# IOTBee-Carrier_v0_1.net
KiCad netlist of a schematic drawn in EAGLE
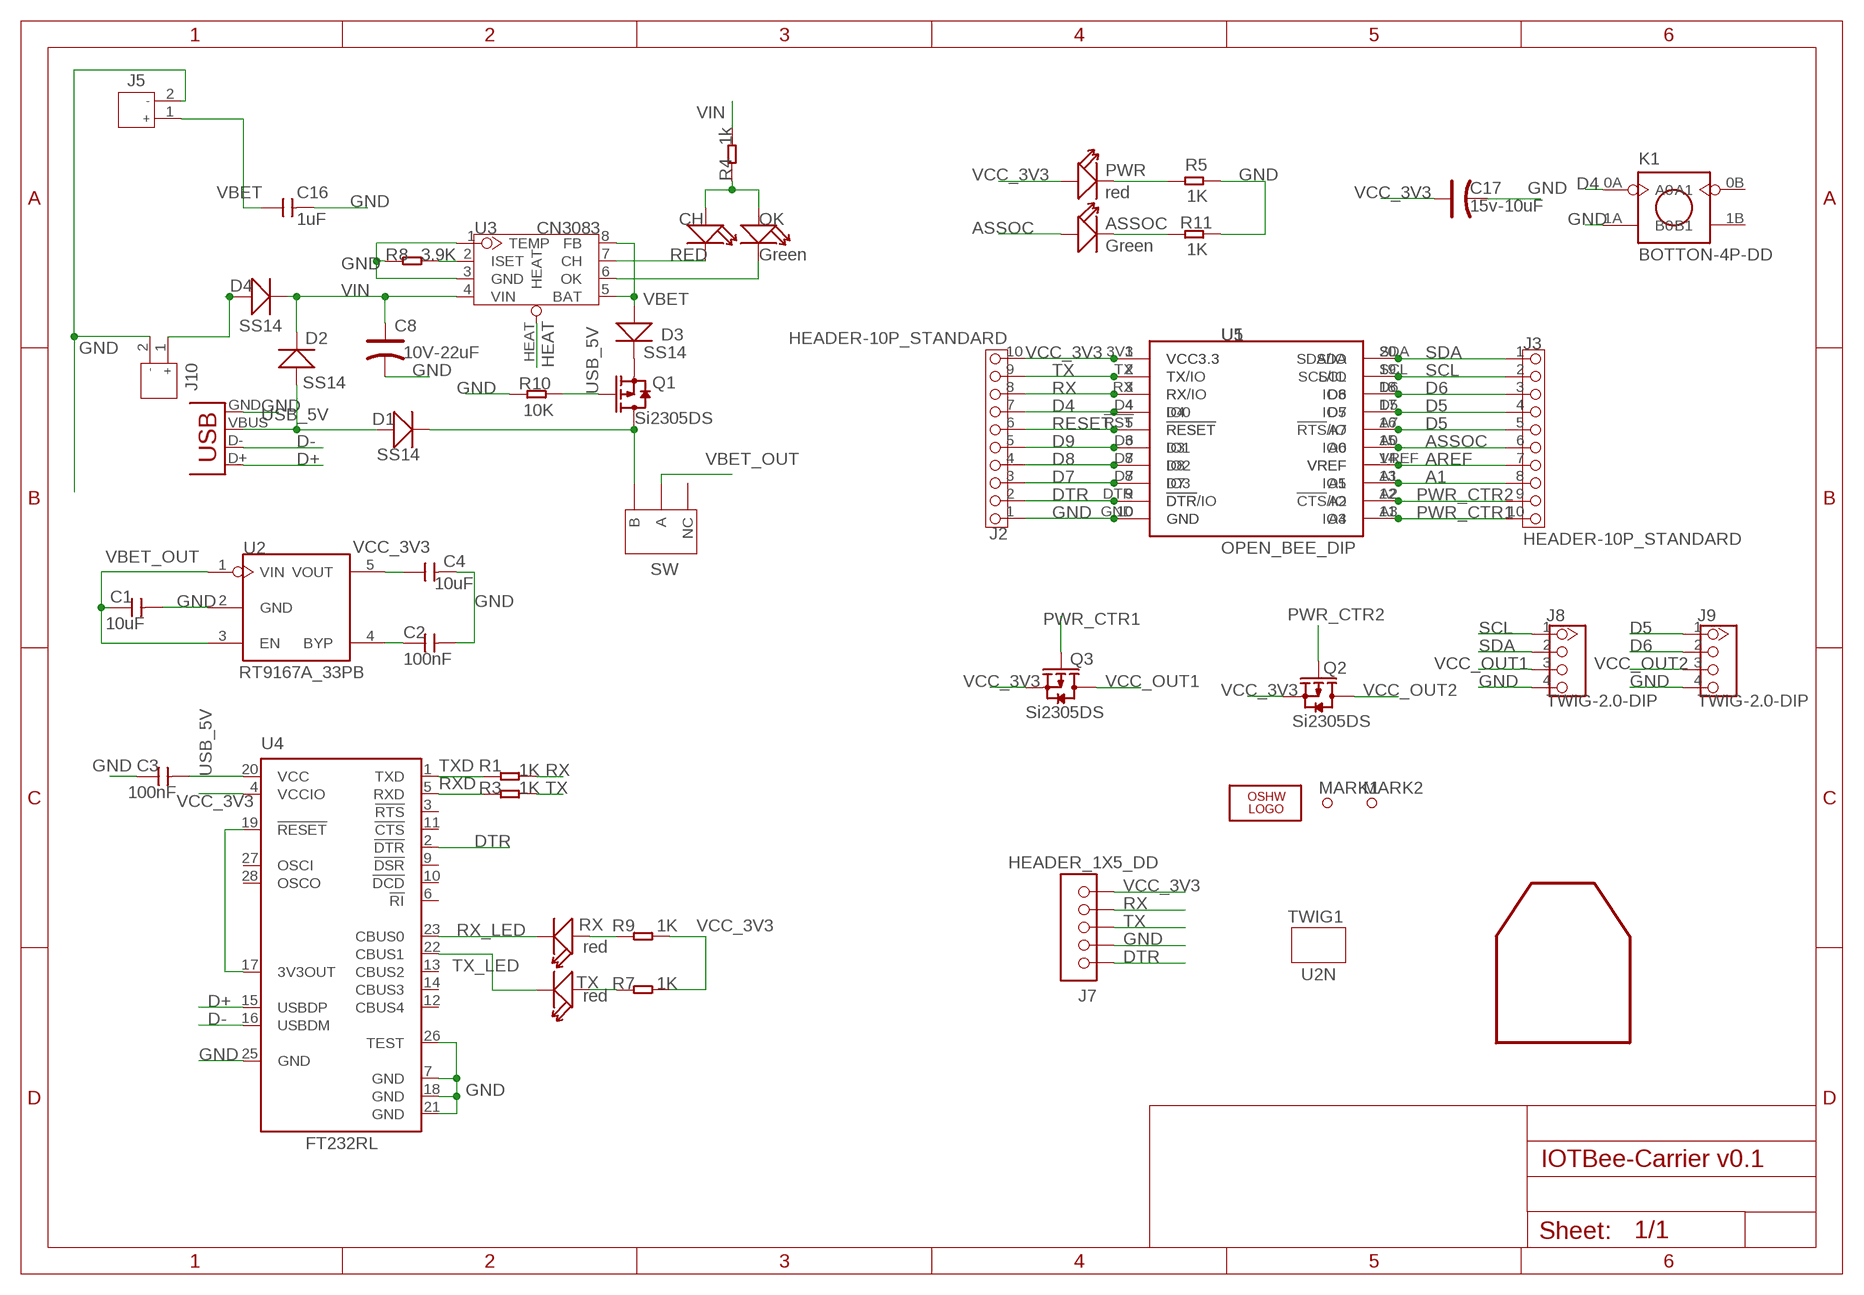
[diagram p0: schematic, sheet 1]

(export (version "E")
  (design (tool "Eeschema 10.0.6"))
  (components
    (comp (ref "ASSOC")
      (value "Green")
      (footprint "eagle-import:D0603")
      (libsource (lib "eagle-import") (part "LED-0603"))
    )
    (comp (ref "C1")
      (value "10uF")
      (footprint "eagle-import:0805")
      (libsource (lib "eagle-import") (part "C-0805"))
    )
    (comp (ref "C2")
      (value "100nF")
      (footprint "eagle-import:0603")
      (libsource (lib "eagle-import") (part "C-0603"))
    )
    (comp (ref "C3")
      (value "100nF")
      (footprint "eagle-import:0603")
      (libsource (lib "eagle-import") (part "C-0603"))
    )
    (comp (ref "C4")
      (value "10uF")
      (footprint "eagle-import:0805")
      (libsource (lib "eagle-import") (part "C-0805"))
    )
    (comp (ref "C8")
      (value "10V-22uF")
      (footprint "eagle-import:AVX-B")
      (libsource (lib "eagle-import") (part "CAP_AVX_B"))
    )
    (comp (ref "C16")
      (value "1uF")
      (footprint "eagle-import:0805")
      (libsource (lib "eagle-import") (part "C-0805"))
    )
    (comp (ref "C17")
      (value "15v-10uF")
      (footprint "eagle-import:AVX-A")
      (libsource (lib "eagle-import") (part "CAP_AVX_A"))
    )
    (comp (ref "CH")
      (value "RED")
      (footprint "eagle-import:D0603")
      (libsource (lib "eagle-import") (part "LED-0603"))
    )
    (comp (ref "D1")
      (value "SS14")
      (footprint "eagle-import:D2010")
      (libsource (lib "eagle-import") (part "D-2010"))
    )
    (comp (ref "D2")
      (value "SS14")
      (footprint "eagle-import:D2010")
      (libsource (lib "eagle-import") (part "D-2010"))
    )
    (comp (ref "D3")
      (value "SS14")
      (footprint "eagle-import:D2010")
      (libsource (lib "eagle-import") (part "D-2010"))
    )
    (comp (ref "D4")
      (value "SS14")
      (footprint "eagle-import:D2010")
      (libsource (lib "eagle-import") (part "D-2010"))
    )
    (comp (ref "J2")
      (value "HEADER-10P_STANDARD")
      (footprint "eagle-import:2.54_10P")
      (libsource (lib "eagle-import") (part "HEADER-10P_STANDARD"))
    )
    (comp (ref "J3")
      (value "HEADER-10P_STANDARD")
      (footprint "eagle-import:2.54_10P")
      (libsource (lib "eagle-import") (part "HEADER-10P_STANDARD"))
    )
    (comp (ref "J5")
      (value "JST-2P-POWER-LEADED")
      (footprint "eagle-import:2P-2.0-LEADED-4.7X6.0")
      (libsource (lib "eagle-import") (part "JST-2P-POWER-LEADED"))
    )
    (comp (ref "J7")
      (value "HEADER_1X5_DD")
      (footprint "eagle-import:CK_1X5")
      (libsource (lib "eagle-import") (part "HEADER_1X5_DD"))
    )
    (comp (ref "J8")
      (value "TWIG-2.0-DIP")
      (footprint "eagle-import:2.0_1X4")
      (libsource (lib "eagle-import") (part "TWIG-2.0-DIP"))
    )
    (comp (ref "J9")
      (value "TWIG-2.0-DIP")
      (footprint "eagle-import:2.0_1X4")
      (libsource (lib "eagle-import") (part "TWIG-2.0-DIP"))
    )
    (comp (ref "J10")
      (value "JST-2P-POWER-LEADED")
      (footprint "eagle-import:2P-2.0-LEADED-4.7X6.0")
      (libsource (lib "eagle-import") (part "JST-2P-POWER-LEADED"))
    )
    (comp (ref "K1")
      (value "BOTTON-4P-DD")
      (footprint "eagle-import:BTN-S")
      (libsource (lib "eagle-import") (part "BOTTON-4P-DD"))
    )
    (comp (ref "LOGO2")
      (value "OSHW_LOGO_FILLX0200-NT")
      (footprint "eagle-import:OSHW_FILLX200_NOTEXT")
      (libsource (lib "eagle-import") (part "OSHW_LOGO_FILLX0200-NT"))
    )
    (comp (ref "MARK1")
      (value "PAD-MARK")
      (footprint "eagle-import:MARK")
      (libsource (lib "eagle-import") (part "PAD-MARK"))
    )
    (comp (ref "MARK2")
      (value "PAD-MARK")
      (footprint "eagle-import:MARK")
      (libsource (lib "eagle-import") (part "PAD-MARK"))
    )
    (comp (ref "OK")
      (value "Green")
      (footprint "eagle-import:D0603")
      (libsource (lib "eagle-import") (part "LED-0603"))
    )
    (comp (ref "PWR")
      (value "red")
      (footprint "eagle-import:D0805")
      (libsource (lib "eagle-import") (part "LED-0805"))
    )
    (comp (ref "Q1")
      (value "Si2305DS")
      (footprint "eagle-import:SOT23")
      (libsource (lib "eagle-import") (part "010-P-MOSFETSOT23"))
    )
    (comp (ref "Q2")
      (value "Si2305DS")
      (footprint "eagle-import:SOT23")
      (libsource (lib "eagle-import") (part "010-P-MOSFETSOT23"))
    )
    (comp (ref "Q3")
      (value "Si2305DS")
      (footprint "eagle-import:SOT23")
      (libsource (lib "eagle-import") (part "010-P-MOSFETSOT23"))
    )
    (comp (ref "R1")
      (value "1K")
      (footprint "eagle-import:0603")
      (libsource (lib "eagle-import") (part "R-0603"))
    )
    (comp (ref "R3")
      (value "1K")
      (footprint "eagle-import:0603")
      (libsource (lib "eagle-import") (part "R-0603"))
    )
    (comp (ref "R4")
      (value "1k")
      (footprint "eagle-import:0603")
      (libsource (lib "eagle-import") (part "R-0603"))
    )
    (comp (ref "R5")
      (value "1K")
      (footprint "eagle-import:0603")
      (libsource (lib "eagle-import") (part "R-0603"))
    )
    (comp (ref "R7")
      (value "1K")
      (footprint "eagle-import:0603")
      (libsource (lib "eagle-import") (part "R-0603"))
    )
    (comp (ref "R8")
      (value "3.9K")
      (footprint "eagle-import:0603")
      (libsource (lib "eagle-import") (part "R-0603"))
    )
    (comp (ref "R9")
      (value "1K")
      (footprint "eagle-import:0603")
      (libsource (lib "eagle-import") (part "R-0603"))
    )
    (comp (ref "R10")
      (value "10K")
      (footprint "eagle-import:0603")
      (libsource (lib "eagle-import") (part "R-0603"))
    )
    (comp (ref "R11")
      (value "1K")
      (footprint "eagle-import:0603")
      (libsource (lib "eagle-import") (part "R-0603"))
    )
    (comp (ref "RX")
      (value "red")
      (footprint "eagle-import:D0603")
      (libsource (lib "eagle-import") (part "LED-0603"))
    )
    (comp (ref "SW")
      (value "SWITCH-3P")
      (footprint "eagle-import:008-SW-3P-DIP")
      (libsource (lib "eagle-import") (part "SWITCH-3P"))
    )
    (comp (ref "TWIG1")
      (value "U2N")
      (footprint "eagle-import:U2N_SILK")
      (libsource (lib "eagle-import") (part "U2N"))
    )
    (comp (ref "TX")
      (value "red")
      (footprint "eagle-import:D0603")
      (libsource (lib "eagle-import") (part "LED-0603"))
    )
    (comp (ref "U$1")
      (value "WIFI_SILK")
      (footprint "eagle-import:WIFI_SILK")
      (libsource (lib "eagle-import") (part "WIFI_SILK"))
    )
    (comp (ref "U1")
      (value "OPEN_BEE_DIP")
      (footprint "eagle-import:CCBEE-PRO")
      (libsource (lib "eagle-import") (part "OPEN_BEE_DIP"))
    )
    (comp (ref "U2")
      (value "RT9167A_33PB")
      (footprint "eagle-import:SOT23-5")
      (libsource (lib "eagle-import") (part "RT9167A"))
    )
    (comp (ref "U3")
      (value "CN3083")
      (footprint "eagle-import:SOP8")
      (libsource (lib "eagle-import") (part "CN3083"))
    )
    (comp (ref "U4")
      (value "FT232RL")
      (footprint "eagle-import:SSOP28")
      (libsource (lib "eagle-import") (part "FT232RL"))
    )
    (comp (ref "U5")
      (value "BEE-IOTBEE-IOTBEE-SOCKET")
      (footprint "eagle-import:IOT_BEE_SMD")
      (libsource (lib "eagle-import") (part "BEE-IOTBEE-IOTBEE-SOCKET"))
    )
    (comp (ref "X1")
      (value "USB-SMD-NS")
      (footprint "eagle-import:USB-MINIB-NOSTOP")
      (libsource (lib "eagle-import") (part "USB-SMD-NS"))
    )
  )
  (nets
    (net (code "1") (name "/A1") (class "Default")
      (node (ref "J3") (pin "8") (pinfunction "8_8") (pintype "bidirectional"))
      (node (ref "U1") (pin "13") (pinfunction "IO5_13") (pintype "bidirectional"))
      (node (ref "U5") (pin "A1") (pinfunction "A1_A1") (pintype "bidirectional"))
    )
    (net (code "2") (name "/AREF") (class "Default")
      (node (ref "J3") (pin "7") (pinfunction "7_7") (pintype "bidirectional"))
      (node (ref "U1") (pin "14") (pinfunction "VREF_14") (pintype "bidirectional"))
      (node (ref "U5") (pin "VREF") (pinfunction "VREF_VREF") (pintype "bidirectional"))
    )
    (net (code "3") (name "/ASSOC") (class "Default")
      (node (ref "ASSOC") (pin "+") (pinfunction "+_+") (pintype "passive"))
      (node (ref "J3") (pin "6") (pinfunction "6_6") (pintype "bidirectional"))
      (node (ref "U1") (pin "15") (pinfunction "IO6_15") (pintype "bidirectional"))
      (node (ref "U5") (pin "A0") (pinfunction "A0_A0") (pintype "bidirectional"))
    )
    (net (code "4") (name "/D+") (class "Default")
      (node (ref "U4") (pin "15") (pinfunction "USBDP_15") (pintype "input"))
      (node (ref "X1") (pin "D+") (pinfunction "D+_D+") (pintype "bidirectional"))
    )
    (net (code "5") (name "/D-") (class "Default")
      (node (ref "U4") (pin "16") (pinfunction "USBDM_16") (pintype "input"))
      (node (ref "X1") (pin "D-") (pinfunction "D-_D-") (pintype "bidirectional"))
    )
    (net (code "6") (name "/D4") (class "Default")
      (node (ref "J2") (pin "7") (pinfunction "7_7") (pintype "bidirectional"))
      (node (ref "K1") (pin "0A") (pinfunction "A0_0A") (pintype "bidirectional"))
      (node (ref "U1") (pin "4") (pinfunction "IO0_4") (pintype "bidirectional"))
      (node (ref "U5") (pin "D4") (pinfunction "D4_D4") (pintype "bidirectional"))
    )
    (net (code "7") (name "/D5") (class "Default")
      (node (ref "J3") (pin "4") (pinfunction "4_4") (pintype "bidirectional"))
      (node (ref "J3") (pin "5") (pinfunction "5_5") (pintype "bidirectional"))
      (node (ref "J9") (pin "1") (pinfunction "1_1") (pintype "bidirectional"))
      (node (ref "U1") (pin "16") (pinfunction "~{RTS}/IO_16") (pintype "bidirectional"))
      (node (ref "U1") (pin "17") (pinfunction "IO7_17") (pintype "bidirectional"))
      (node (ref "U5") (pin "A7") (pinfunction "A7_A7") (pintype "bidirectional"))
      (node (ref "U5") (pin "D5") (pinfunction "D5_D5") (pintype "bidirectional"))
    )
    (net (code "8") (name "/D6") (class "Default")
      (node (ref "J3") (pin "3") (pinfunction "3_3") (pintype "bidirectional"))
      (node (ref "J9") (pin "2") (pinfunction "2_2") (pintype "bidirectional"))
      (node (ref "U1") (pin "18") (pinfunction "IO8_18") (pintype "bidirectional"))
      (node (ref "U5") (pin "D6") (pinfunction "D6_D6") (pintype "bidirectional"))
    )
    (net (code "9") (name "/D7") (class "Default")
      (node (ref "J2") (pin "3") (pinfunction "3_3") (pintype "bidirectional"))
      (node (ref "U1") (pin "8") (pinfunction "IO3_8") (pintype "bidirectional"))
      (node (ref "U5") (pin "D7") (pinfunction "D7_D7") (pintype "bidirectional"))
    )
    (net (code "10") (name "/D8") (class "Default")
      (node (ref "J2") (pin "4") (pinfunction "4_4") (pintype "bidirectional"))
      (node (ref "U1") (pin "7") (pinfunction "IO2_7") (pintype "bidirectional"))
      (node (ref "U5") (pin "D8") (pinfunction "D8_D8") (pintype "bidirectional"))
    )
    (net (code "11") (name "/D9") (class "Default")
      (node (ref "J2") (pin "5") (pinfunction "5_5") (pintype "bidirectional"))
      (node (ref "U1") (pin "6") (pinfunction "IO1_6") (pintype "bidirectional"))
      (node (ref "U5") (pin "D3") (pinfunction "D3_D3") (pintype "bidirectional"))
    )
    (net (code "12") (name "/DTR") (class "Default")
      (node (ref "J2") (pin "2") (pinfunction "2_2") (pintype "bidirectional"))
      (node (ref "J7") (pin "1") (pinfunction "1_1") (pintype "bidirectional"))
      (node (ref "U1") (pin "9") (pinfunction "~{DTR}/IO_9") (pintype "bidirectional"))
      (node (ref "U4") (pin "2") (pinfunction "~{DTR}_2") (pintype "input"))
      (node (ref "U5") (pin "DTR") (pinfunction "~{DTR}_DTR") (pintype "bidirectional"))
    )
    (net (code "13") (name "/GND") (class "Default")
      (node (ref "C1") (pin "2") (pinfunction "2_2") (pintype "passive"))
      (node (ref "C16") (pin "2") (pinfunction "2_2") (pintype "passive"))
      (node (ref "C17") (pin "-") (pinfunction "-_-") (pintype "passive"))
      (node (ref "C2") (pin "2") (pinfunction "2_2") (pintype "passive"))
      (node (ref "C3") (pin "1") (pinfunction "1_1") (pintype "passive"))
      (node (ref "C4") (pin "2") (pinfunction "2_2") (pintype "passive"))
      (node (ref "C8") (pin "-") (pinfunction "-_-") (pintype "passive"))
      (node (ref "J10") (pin "2") (pinfunction "P$2_2") (pintype "bidirectional"))
      (node (ref "J2") (pin "1") (pinfunction "1_1") (pintype "bidirectional"))
      (node (ref "J5") (pin "2") (pinfunction "P$2_2") (pintype "bidirectional"))
      (node (ref "J7") (pin "2") (pinfunction "2_2") (pintype "bidirectional"))
      (node (ref "J8") (pin "4") (pinfunction "4_4") (pintype "bidirectional"))
      (node (ref "J9") (pin "4") (pinfunction "4_4") (pintype "bidirectional"))
      (node (ref "K1") (pin "1A") (pinfunction "B0_1A") (pintype "bidirectional"))
      (node (ref "R10") (pin "1") (pinfunction "1_1") (pintype "passive"))
      (node (ref "R11") (pin "1") (pinfunction "1_1") (pintype "passive"))
      (node (ref "R5") (pin "1") (pinfunction "1_1") (pintype "passive"))
      (node (ref "R8") (pin "1") (pinfunction "1_1") (pintype "passive"))
      (node (ref "U1") (pin "10") (pinfunction "GND_10") (pintype "bidirectional"))
      (node (ref "U2") (pin "2") (pinfunction "GND_2") (pintype "bidirectional"))
      (node (ref "U3") (pin "1") (pinfunction "TEMP_1") (pintype "bidirectional"))
      (node (ref "U3") (pin "3") (pinfunction "GND_3") (pintype "bidirectional"))
      (node (ref "U4") (pin "18") (pinfunction "GND_18") (pintype "input"))
      (node (ref "U4") (pin "21") (pinfunction "GND_21") (pintype "input"))
      (node (ref "U4") (pin "25") (pinfunction "GND_25") (pintype "input"))
      (node (ref "U4") (pin "26") (pinfunction "TEST_26") (pintype "input"))
      (node (ref "U4") (pin "7") (pinfunction "GND_7") (pintype "input"))
      (node (ref "U5") (pin "GND") (pinfunction "GND_GND") (pintype "bidirectional"))
      (node (ref "X1") (pin "GND") (pinfunction "GND_GND") (pintype "bidirectional"))
    )
    (net (code "14") (name "/HEAT") (class "Default")
      (node (ref "U3") (pin "HEAT") (pinfunction "HEAT_HEAT") (pintype "bidirectional"))
    )
    (net (code "15") (name "/PWR_CTR1") (class "Default")
      (node (ref "J3") (pin "10") (pinfunction "10_10") (pintype "bidirectional"))
      (node (ref "Q3") (pin "1") (pinfunction "G_1") (pintype "passive"))
      (node (ref "U1") (pin "11") (pinfunction "IO4_11") (pintype "bidirectional"))
      (node (ref "U5") (pin "A3") (pinfunction "A3_A3") (pintype "bidirectional"))
    )
    (net (code "16") (name "/PWR_CTR2") (class "Default")
      (node (ref "J3") (pin "9") (pinfunction "9_9") (pintype "bidirectional"))
      (node (ref "Q2") (pin "1") (pinfunction "G_1") (pintype "passive"))
      (node (ref "U1") (pin "12") (pinfunction "~{CTS}/IO_12") (pintype "bidirectional"))
      (node (ref "U5") (pin "A2") (pinfunction "A2_A2") (pintype "bidirectional"))
    )
    (net (code "17") (name "/RESET") (class "Default")
      (node (ref "J2") (pin "6") (pinfunction "6_6") (pintype "bidirectional"))
      (node (ref "U1") (pin "5") (pinfunction "~{RESET}_5") (pintype "bidirectional"))
      (node (ref "U5") (pin "!RST") (pinfunction "~{RESET}_!RST") (pintype "bidirectional"))
    )
    (net (code "18") (name "/RX") (class "Default")
      (node (ref "J2") (pin "8") (pinfunction "8_8") (pintype "bidirectional"))
      (node (ref "J7") (pin "4") (pinfunction "4_4") (pintype "bidirectional"))
      (node (ref "R1") (pin "2") (pinfunction "2_2") (pintype "passive"))
      (node (ref "U1") (pin "3") (pinfunction "RX/IO_3") (pintype "bidirectional"))
      (node (ref "U5") (pin "RX") (pinfunction "RX_RX") (pintype "bidirectional"))
    )
    (net (code "19") (name "/RXD") (class "Default")
      (node (ref "R3") (pin "1") (pinfunction "1_1") (pintype "passive"))
      (node (ref "U4") (pin "5") (pinfunction "RXD_5") (pintype "input"))
    )
    (net (code "20") (name "/RX_LED") (class "Default")
      (node (ref "RX") (pin "-") (pinfunction "-_-") (pintype "passive"))
      (node (ref "U4") (pin "23") (pinfunction "CBUS0_23") (pintype "input"))
    )
    (net (code "21") (name "/SCL") (class "Default")
      (node (ref "J3") (pin "2") (pinfunction "2_2") (pintype "bidirectional"))
      (node (ref "J8") (pin "1") (pinfunction "1_1") (pintype "bidirectional"))
      (node (ref "U1") (pin "19") (pinfunction "SCL/IO_19") (pintype "bidirectional"))
      (node (ref "U5") (pin "SCL") (pinfunction "SCL_SCL") (pintype "bidirectional"))
    )
    (net (code "22") (name "/SDA") (class "Default")
      (node (ref "J3") (pin "1") (pinfunction "1_1") (pintype "bidirectional"))
      (node (ref "J8") (pin "2") (pinfunction "2_2") (pintype "bidirectional"))
      (node (ref "U1") (pin "20") (pinfunction "SDA/IO_20") (pintype "bidirectional"))
      (node (ref "U5") (pin "SDA") (pinfunction "SDA_SDA") (pintype "bidirectional"))
    )
    (net (code "23") (name "/TX") (class "Default")
      (node (ref "J2") (pin "9") (pinfunction "9_9") (pintype "bidirectional"))
      (node (ref "J7") (pin "3") (pinfunction "3_3") (pintype "bidirectional"))
      (node (ref "R3") (pin "2") (pinfunction "2_2") (pintype "passive"))
      (node (ref "U1") (pin "2") (pinfunction "TX/IO_2") (pintype "bidirectional"))
      (node (ref "U5") (pin "TX") (pinfunction "TX_TX") (pintype "bidirectional"))
    )
    (net (code "24") (name "/TXD") (class "Default")
      (node (ref "R1") (pin "1") (pinfunction "1_1") (pintype "passive"))
      (node (ref "U4") (pin "1") (pinfunction "TXD_1") (pintype "input"))
    )
    (net (code "25") (name "/TX_LED") (class "Default")
      (node (ref "TX") (pin "-") (pinfunction "-_-") (pintype "passive"))
      (node (ref "U4") (pin "22") (pinfunction "CBUS1_22") (pintype "input"))
    )
    (net (code "26") (name "/USB_5V") (class "Default")
      (node (ref "C3") (pin "2") (pinfunction "2_2") (pintype "passive"))
      (node (ref "D1") (pin "+") (pinfunction "+_+") (pintype "passive"))
      (node (ref "D2") (pin "+") (pinfunction "+_+") (pintype "passive"))
      (node (ref "Q1") (pin "1") (pinfunction "G_1") (pintype "passive"))
      (node (ref "R10") (pin "2") (pinfunction "2_2") (pintype "passive"))
      (node (ref "U4") (pin "20") (pinfunction "VCC_20") (pintype "input"))
      (node (ref "X1") (pin "VBUS") (pinfunction "VBUS_VBUS") (pintype "bidirectional"))
    )
    (net (code "27") (name "/VBET") (class "Default")
      (node (ref "C16") (pin "1") (pinfunction "1_1") (pintype "passive"))
      (node (ref "D3") (pin "+") (pinfunction "+_+") (pintype "passive"))
      (node (ref "J5") (pin "1") (pinfunction "P$1_1") (pintype "bidirectional"))
      (node (ref "U3") (pin "5") (pinfunction "BAT_5") (pintype "bidirectional"))
      (node (ref "U3") (pin "8") (pinfunction "FB_8") (pintype "bidirectional"))
    )
    (net (code "28") (name "/VBET_OUT") (class "Default")
      (node (ref "C1") (pin "1") (pinfunction "1_1") (pintype "passive"))
      (node (ref "SW") (pin "P$2") (pinfunction "A_P$2") (pintype "bidirectional"))
      (node (ref "U2") (pin "1") (pinfunction "VIN_1") (pintype "bidirectional"))
      (node (ref "U2") (pin "3") (pinfunction "EN_3") (pintype "bidirectional"))
    )
    (net (code "29") (name "/VCC_3V3") (class "Default")
      (node (ref "C17") (pin "+") (pinfunction "+_+") (pintype "passive"))
      (node (ref "C4") (pin "1") (pinfunction "1_1") (pintype "passive"))
      (node (ref "J2") (pin "10") (pinfunction "10_10") (pintype "bidirectional"))
      (node (ref "J7") (pin "5") (pinfunction "5_5") (pintype "bidirectional"))
      (node (ref "PWR") (pin "+") (pinfunction "+_+") (pintype "passive"))
      (node (ref "Q2") (pin "2") (pinfunction "S_2") (pintype "passive"))
      (node (ref "Q3") (pin "2") (pinfunction "S_2") (pintype "passive"))
      (node (ref "R7") (pin "2") (pinfunction "2_2") (pintype "passive"))
      (node (ref "R9") (pin "2") (pinfunction "2_2") (pintype "passive"))
      (node (ref "U1") (pin "1") (pinfunction "VCC3.3_1") (pintype "bidirectional"))
      (node (ref "U2") (pin "5") (pinfunction "VOUT_5") (pintype "bidirectional"))
      (node (ref "U4") (pin "4") (pinfunction "VCCIO_4") (pintype "input"))
      (node (ref "U5") (pin "3V3") (pinfunction "VCC3.3_3V3") (pintype "bidirectional"))
    )
    (net (code "30") (name "/VCC_OUT1") (class "Default")
      (node (ref "J8") (pin "3") (pinfunction "3_3") (pintype "bidirectional"))
      (node (ref "Q3") (pin "3") (pinfunction "D_3") (pintype "passive"))
    )
    (net (code "31") (name "/VCC_OUT2") (class "Default")
      (node (ref "J9") (pin "3") (pinfunction "3_3") (pintype "bidirectional"))
      (node (ref "Q2") (pin "3") (pinfunction "D_3") (pintype "passive"))
    )
    (net (code "32") (name "/VIN") (class "Default")
      (node (ref "C8") (pin "+") (pinfunction "+_+") (pintype "passive"))
      (node (ref "D2") (pin "-") (pinfunction "-_-") (pintype "passive"))
      (node (ref "D4") (pin "-") (pinfunction "-_-") (pintype "passive"))
      (node (ref "R4") (pin "2") (pinfunction "2_2") (pintype "passive"))
      (node (ref "U3") (pin "4") (pinfunction "VIN_4") (pintype "bidirectional"))
    )
    (net (code "33") (name "Net-(ASSOC-Pad-)") (class "Default")
      (node (ref "ASSOC") (pin "-") (pinfunction "-_-") (pintype "passive"))
      (node (ref "R11") (pin "2") (pinfunction "2_2") (pintype "passive"))
    )
    (net (code "34") (name "Net-(CH-Pad+)") (class "Default")
      (node (ref "CH") (pin "+") (pinfunction "+_+") (pintype "passive"))
      (node (ref "OK") (pin "+") (pinfunction "+_+") (pintype "passive"))
      (node (ref "R4") (pin "1") (pinfunction "1_1") (pintype "passive"))
    )
    (net (code "35") (name "Net-(J10-P$1)") (class "Default")
      (node (ref "D4") (pin "+") (pinfunction "+_+") (pintype "passive"))
      (node (ref "J10") (pin "1") (pinfunction "P$1_1") (pintype "bidirectional"))
    )
    (net (code "36") (name "Net-(PWR-Pad-)") (class "Default")
      (node (ref "PWR") (pin "-") (pinfunction "-_-") (pintype "passive"))
      (node (ref "R5") (pin "2") (pinfunction "2_2") (pintype "passive"))
    )
    (net (code "37") (name "Net-(Q1-D)") (class "Default")
      (node (ref "D1") (pin "-") (pinfunction "-_-") (pintype "passive"))
      (node (ref "Q1") (pin "3") (pinfunction "D_3") (pintype "passive"))
      (node (ref "SW") (pin "P$3") (pinfunction "B_P$3") (pintype "bidirectional"))
    )
    (net (code "38") (name "Net-(Q1-S)") (class "Default")
      (node (ref "D3") (pin "-") (pinfunction "-_-") (pintype "passive"))
      (node (ref "Q1") (pin "2") (pinfunction "S_2") (pintype "passive"))
    )
    (net (code "39") (name "Net-(R7-Pad1)") (class "Default")
      (node (ref "R7") (pin "1") (pinfunction "1_1") (pintype "passive"))
      (node (ref "TX") (pin "+") (pinfunction "+_+") (pintype "passive"))
    )
    (net (code "40") (name "Net-(R9-Pad1)") (class "Default")
      (node (ref "R9") (pin "1") (pinfunction "1_1") (pintype "passive"))
      (node (ref "RX") (pin "+") (pinfunction "+_+") (pintype "passive"))
    )
    (net (code "41") (name "Net-(U2-BYP)") (class "Default")
      (node (ref "C2") (pin "1") (pinfunction "1_1") (pintype "passive"))
      (node (ref "U2") (pin "4") (pinfunction "BYP_4") (pintype "bidirectional"))
    )
    (net (code "42") (name "Net-(U3-CH)") (class "Default")
      (node (ref "CH") (pin "-") (pinfunction "-_-") (pintype "passive"))
      (node (ref "U3") (pin "7") (pinfunction "CH_7") (pintype "bidirectional"))
    )
    (net (code "43") (name "Net-(U3-ISET)") (class "Default")
      (node (ref "R8") (pin "2") (pinfunction "2_2") (pintype "passive"))
      (node (ref "U3") (pin "2") (pinfunction "ISET_2") (pintype "bidirectional"))
    )
    (net (code "44") (name "Net-(U3-OK)") (class "Default")
      (node (ref "OK") (pin "-") (pinfunction "-_-") (pintype "passive"))
      (node (ref "U3") (pin "6") (pinfunction "OK_6") (pintype "bidirectional"))
    )
    (net (code "45") (name "Net-(U4-3V3OUT)") (class "Default")
      (node (ref "U4") (pin "17") (pinfunction "3V3OUT_17") (pintype "input"))
      (node (ref "U4") (pin "19") (pinfunction "~{RESET}_19") (pintype "input"))
    )
    (net (code "46") (name "unconnected-(K1-A1-Pad0B)") (class "Default")
      (node (ref "K1") (pin "0B") (pinfunction "A1_0B") (pintype "bidirectional"))
    )
    (net (code "47") (name "unconnected-(K1-B1-Pad1B)") (class "Default")
      (node (ref "K1") (pin "1B") (pinfunction "B1_1B") (pintype "bidirectional"))
    )
    (net (code "48") (name "unconnected-(SW-NC-PadP$1)") (class "Default")
      (node (ref "SW") (pin "P$1") (pinfunction "NC_P$1") (pintype "no_connect"))
    )
    (net (code "49") (name "unconnected-(U4-CBUS2-Pad13)") (class "Default")
      (node (ref "U4") (pin "13") (pinfunction "CBUS2_13") (pintype "input"))
    )
    (net (code "50") (name "unconnected-(U4-CBUS3-Pad14)") (class "Default")
      (node (ref "U4") (pin "14") (pinfunction "CBUS3_14") (pintype "input"))
    )
    (net (code "51") (name "unconnected-(U4-CBUS4-Pad12)") (class "Default")
      (node (ref "U4") (pin "12") (pinfunction "CBUS4_12") (pintype "input"))
    )
    (net (code "52") (name "unconnected-(U4-OSCI-Pad27)") (class "Default")
      (node (ref "U4") (pin "27") (pinfunction "OSCI_27") (pintype "input"))
    )
    (net (code "53") (name "unconnected-(U4-OSCO-Pad28)") (class "Default")
      (node (ref "U4") (pin "28") (pinfunction "OSCO_28") (pintype "input"))
    )
    (net (code "54") (name "unconnected-(U4-~{CTS}-Pad11)") (class "Default")
      (node (ref "U4") (pin "11") (pinfunction "~{CTS}_11") (pintype "input"))
    )
    (net (code "55") (name "unconnected-(U4-~{DCD}-Pad10)") (class "Default")
      (node (ref "U4") (pin "10") (pinfunction "~{DCD}_10") (pintype "input"))
    )
    (net (code "56") (name "unconnected-(U4-~{DSR}-Pad9)") (class "Default")
      (node (ref "U4") (pin "9") (pinfunction "~{DSR}_9") (pintype "input"))
    )
    (net (code "57") (name "unconnected-(U4-~{RI}-Pad6)") (class "Default")
      (node (ref "U4") (pin "6") (pinfunction "~{RI}_6") (pintype "input"))
    )
    (net (code "58") (name "unconnected-(U4-~{RTS}-Pad3)") (class "Default")
      (node (ref "U4") (pin "3") (pinfunction "~{RTS}_3") (pintype "input"))
    )
  )
)
